# CH32F203K8T6-R0.net
KiCad netlist of a schematic drawn in Altium Designer
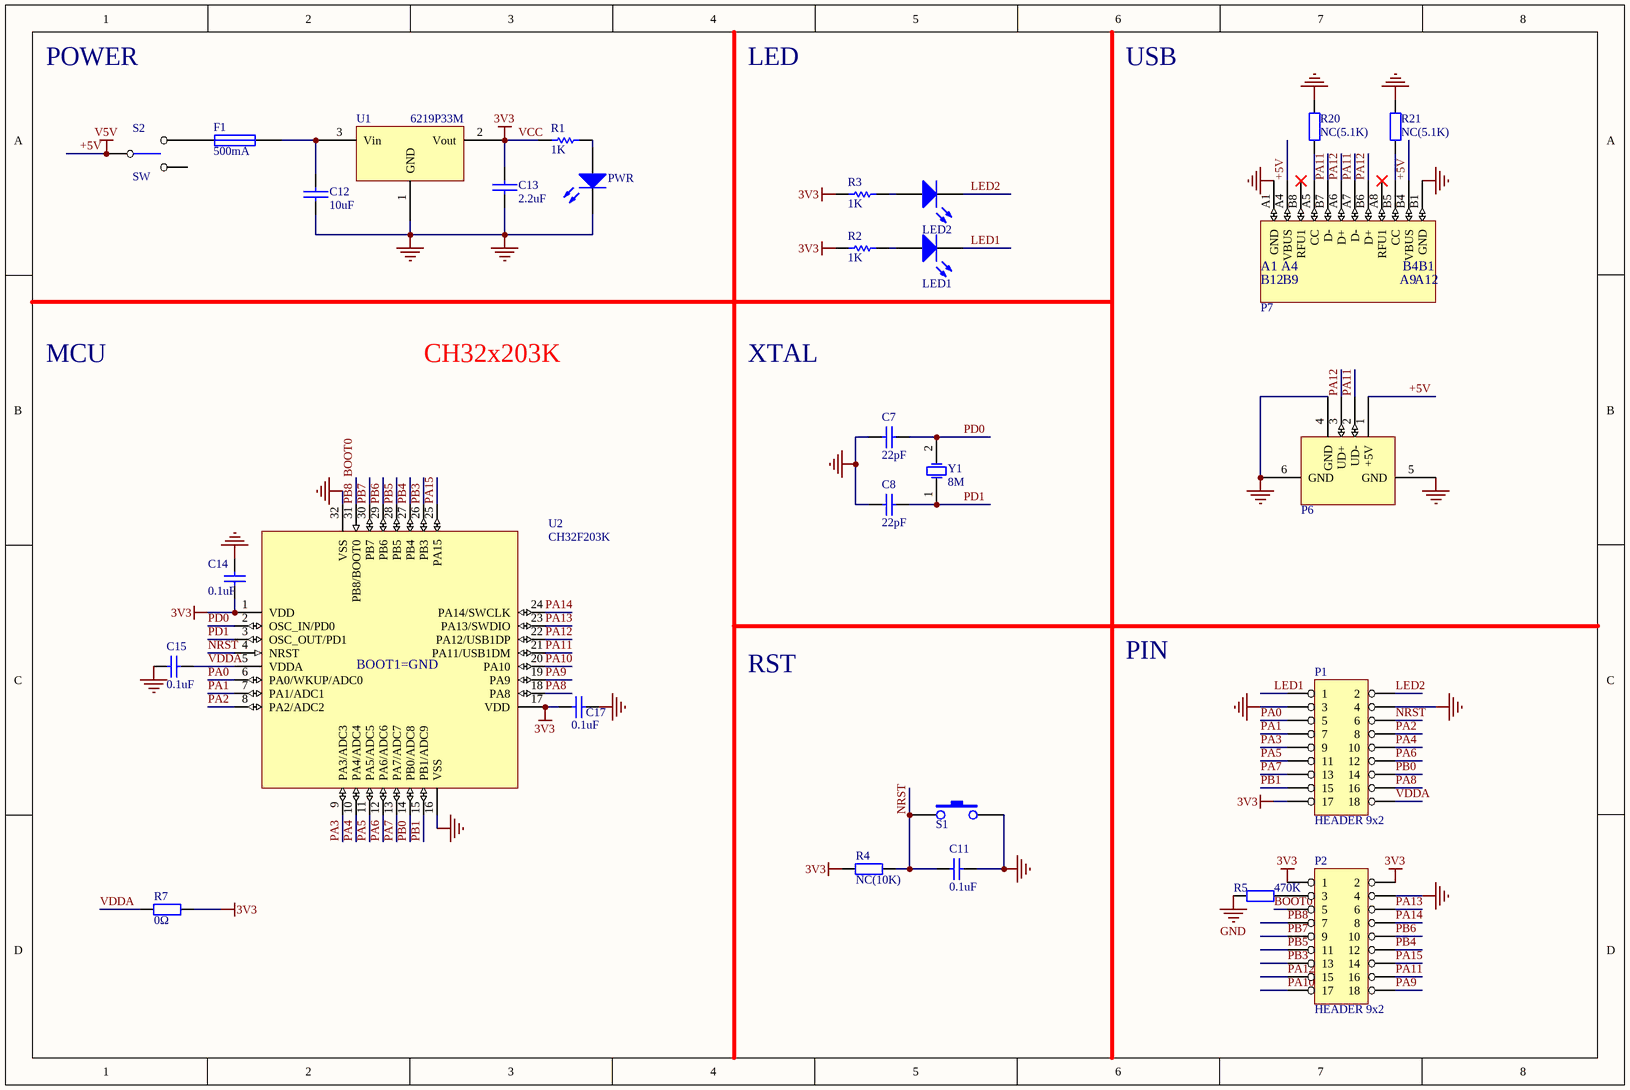
[diagram p0: CH32F203K8T6-R0.SchDoc]

(export (version "E")
  (design (tool "Eeschema 10.0.6"))
  (components
    (comp (ref "C7")
      (value "22pF")
      (footprint "0603_C")
      (description "Capacitor")
      (fields (field (name "PUBLISHER") "Altium Limited"))
      (libsource (lib "*") (part "Cap"))
    )
    (comp (ref "C8")
      (value "22pF")
      (footprint "0603_C")
      (description "Capacitor")
      (fields (field (name "PUBLISHER") "Altium Limited"))
      (libsource (lib "*") (part "Cap"))
    )
    (comp (ref "C11")
      (value "0.1uF")
      (footprint "0603_C")
      (description "Capacitor")
      (fields (field (name "PUBLISHER") "Altium Limited"))
      (libsource (lib "*") (part "Cap"))
    )
    (comp (ref "C12")
      (value "10uF")
      (footprint "3216_C")
      (description "Capacitor")
      (libsource (lib "wch_sch_others") (part "CAP"))
    )
    (comp (ref "C13")
      (value "2.2uF")
      (footprint "0603_C")
      (description "Capacitor")
      (libsource (lib "wch_sch_others") (part "CAP"))
    )
    (comp (ref "C14")
      (value "0.1uF")
      (footprint "0603_C")
      (description "Capacitor")
      (fields (field (name "PUBLISHER") "Altium Limited"))
      (libsource (lib "*") (part "Cap"))
    )
    (comp (ref "C15")
      (value "0.1uF")
      (footprint "0603_C")
      (description "Capacitor")
      (fields (field (name "PUBLISHER") "Altium Limited"))
      (libsource (lib "*") (part "Cap"))
    )
    (comp (ref "C17")
      (value "0.1uF")
      (footprint "0603_C")
      (description "Capacitor")
      (fields (field (name "PUBLISHER") "Altium Limited"))
      (libsource (lib "*") (part "Cap"))
    )
    (comp (ref "F1")
      (value "500mA")
      (footprint "0603")
      (description "Fuse")
      (libsource (lib "*") (part "FUSE1"))
    )
    (comp (ref "LED1")
      (value "LED1   blue")
      (footprint "0603+")
      (description "Typical INFRARED GaAs LED")
      (fields (field (name "PUBLISHER") "Altium Limited"))
      (libsource (lib "*") (part "LED0"))
    )
    (comp (ref "LED2")
      (value "LED2  blue")
      (footprint "0603+")
      (description "Typical INFRARED GaAs LED")
      (fields (field (name "PUBLISHER") "Altium Limited"))
      (libsource (lib "*") (part "LED0"))
    )
    (comp (ref "P1")
      (value "HEADER 9x2")
      (footprint "MYPCB:IDC18-2.54MM")
      (description "Header, 9-Pin, Dual row")
      (libsource (lib "wch_sch_others") (part "HEADER 9x2"))
    )
    (comp (ref "P2")
      (value "HEADER 9x2")
      (footprint "MYPCB:IDC18-2.54MM")
      (description "Header, 9-Pin, Dual row")
      (libsource (lib "wch_sch_others") (part "HEADER 9x2"))
    )
    (comp (ref "P6")
      (value "USB_A")
      (footprint "USBAF")
      (description "USB Port")
      (libsource (lib "*") (part "USB"))
    )
    (comp (ref "P7")
      (value "TYPE-C")
      (footprint "TYPE-C-Receptacle-2.0")
      (libsource (lib "*") (part "TYPE-C1"))
    )
    (comp (ref "PWR")
      (value "POWER  red")
      (footprint "0603+")
      (description "Typical INFRARED GaAs LED")
      (fields (field (name "PUBLISHER") "Altium Limited"))
      (libsource (lib "*") (part "LED0"))
    )
    (comp (ref "R1")
      (value "1K")
      (footprint "0603")
      (description "Semiconductor Resistor")
      (fields (field (name "PUBLISHER") "Altium Limited"))
      (libsource (lib "*") (part "Res Semi"))
    )
    (comp (ref "R2")
      (value "1K")
      (footprint "0603")
      (description "Semiconductor Resistor")
      (fields (field (name "PUBLISHER") "Altium Limited"))
      (libsource (lib "*") (part "Res Semi"))
    )
    (comp (ref "R3")
      (value "1K")
      (footprint "0603")
      (description "Semiconductor Resistor")
      (fields (field (name "PUBLISHER") "Altium Limited"))
      (libsource (lib "*") (part "Res Semi"))
    )
    (comp (ref "R4")
      (value "NC(10K)")
      (footprint "0603")
      (description "Resistor")
      (fields (field (name "PUBLISHER") "Altium Limited"))
      (libsource (lib "*") (part "Res2"))
    )
    (comp (ref "R5")
      (value "470K")
      (footprint "0603")
      (description "Resistor")
      (fields (field (name "PUBLISHER") "Altium Limited"))
      (libsource (lib "") (part "Res2_1"))
    )
    (comp (ref "R7")
      (value "0Ω")
      (footprint "0603")
      (description "Resistor")
      (fields (field (name "PUBLISHER") "Altium Limited"))
      (libsource (lib "*") (part "Res2"))
    )
    (comp (ref "R20")
      (value "NC(5.1K)")
      (footprint "0603")
      (description "Resistor")
      (libsource (lib "Miscellaneous Devices") (part "Res2"))
    )
    (comp (ref "R21")
      (value "NC(5.1K)")
      (footprint "0603")
      (description "Resistor")
      (libsource (lib "Miscellaneous Devices") (part "Res2"))
    )
    (comp (ref "S1") (value "RST") (footprint "SMD_6.1x3.65x2.5mm-KEY") (libsource (lib "*") (part "KEY")))
    (comp (ref "S2") (value "SW") (footprint "KEY2") (libsource (lib "*") (part "SW")))
    (comp (ref "U1")
      (value "6219P33M")
      (footprint "SOT-23")
      (libsource (lib "wch_sch_others") (part "6219P33M"))
    )
    (comp (ref "U2")
      (value "CH32F203K")
      (footprint "LQFP32")
      (description "ARM M3 LMD-MCU, 144MHz, USB FS, CAN")
      (libsource (lib "CHXXX") (part "CH32F203K"))
    )
    (comp (ref "Y1")
      (value "8M")
      (footprint "XT_AT49")
      (description "Crystal Oscillator")
      (fields (field (name "PUBLISHER") "Altium Limited"))
      (libsource (lib "*") (part "XTAL"))
    )
  )
  (nets
    (net (code "2") (name "/BOOT0") (class "Default")
      (node (ref "P2") (pin "5") (pinfunction "5_5") (pintype "passive"))
      (node (ref "P2") (pin "7") (pinfunction "7_7") (pintype "passive"))
      (node (ref "U2") (pin "31") (pinfunction "PB8/BOOT0_31") (pintype "input"))
    )
    (net (code "3") (name "/LED1") (class "Default")
      (node (ref "LED1") (pin "2") (pinfunction "K_2") (pintype "passive"))
      (node (ref "P1") (pin "1") (pinfunction "1_1") (pintype "passive"))
    )
    (net (code "4") (name "/LED2") (class "Default")
      (node (ref "LED2") (pin "2") (pinfunction "K_2") (pintype "passive"))
      (node (ref "P1") (pin "2") (pinfunction "2_2") (pintype "passive"))
    )
    (net (code "5") (name "/NRST") (class "Default")
      (node (ref "C11") (pin "2") (pinfunction "2_2") (pintype "passive"))
      (node (ref "P1") (pin "6") (pinfunction "6_6") (pintype "passive"))
      (node (ref "R4") (pin "1") (pinfunction "1_1") (pintype "passive"))
      (node (ref "S1") (pin "1") (pinfunction "1_1") (pintype "passive"))
      (node (ref "U2") (pin "4") (pinfunction "NRST_4") (pintype "input"))
    )
    (net (code "6") (name "/PA0") (class "Default")
      (node (ref "P1") (pin "5") (pinfunction "5_5") (pintype "passive"))
      (node (ref "U2") (pin "6") (pinfunction "PA0/WKUP/ADC0_6") (pintype "bidirectional"))
    )
    (net (code "7") (name "/PA1") (class "Default")
      (node (ref "P1") (pin "7") (pinfunction "7_7") (pintype "passive"))
      (node (ref "U2") (pin "7") (pinfunction "PA1/ADC1_7") (pintype "bidirectional"))
    )
    (net (code "8") (name "/PA2") (class "Default")
      (node (ref "P1") (pin "8") (pinfunction "8_8") (pintype "passive"))
      (node (ref "U2") (pin "8") (pinfunction "PA2/ADC2_8") (pintype "bidirectional"))
    )
    (net (code "9") (name "/PA3") (class "Default")
      (node (ref "P1") (pin "9") (pinfunction "9_9") (pintype "passive"))
      (node (ref "U2") (pin "9") (pinfunction "PA3/ADC3_9") (pintype "bidirectional"))
    )
    (net (code "10") (name "/PA4") (class "Default")
      (node (ref "P1") (pin "10") (pinfunction "10_10") (pintype "passive"))
      (node (ref "U2") (pin "10") (pinfunction "PA4/ADC4_10") (pintype "bidirectional"))
    )
    (net (code "11") (name "/PA5") (class "Default")
      (node (ref "P1") (pin "11") (pinfunction "11_11") (pintype "passive"))
      (node (ref "U2") (pin "11") (pinfunction "PA5/ADC5_11") (pintype "bidirectional"))
    )
    (net (code "12") (name "/PA6") (class "Default")
      (node (ref "P1") (pin "12") (pinfunction "12_12") (pintype "passive"))
      (node (ref "U2") (pin "12") (pinfunction "PA6/ADC6_12") (pintype "bidirectional"))
    )
    (net (code "13") (name "/PA7") (class "Default")
      (node (ref "P1") (pin "13") (pinfunction "13_13") (pintype "passive"))
      (node (ref "U2") (pin "13") (pinfunction "PA7/ADC7_13") (pintype "bidirectional"))
    )
    (net (code "14") (name "/PA8") (class "Default")
      (node (ref "P1") (pin "16") (pinfunction "16_16") (pintype "passive"))
      (node (ref "U2") (pin "18") (pinfunction "PA8_18") (pintype "bidirectional"))
    )
    (net (code "15") (name "/PA9") (class "Default")
      (node (ref "P2") (pin "18") (pinfunction "18_18") (pintype "passive"))
      (node (ref "U2") (pin "19") (pinfunction "PA9_19") (pintype "bidirectional"))
    )
    (net (code "16") (name "/PA10") (class "Default")
      (node (ref "P2") (pin "17") (pinfunction "17_17") (pintype "passive"))
      (node (ref "U2") (pin "20") (pinfunction "PA10_20") (pintype "bidirectional"))
    )
    (net (code "17") (name "/PA11") (class "Default")
      (node (ref "P2") (pin "16") (pinfunction "16_16") (pintype "passive"))
      (node (ref "P6") (pin "2") (pinfunction "UD-_2") (pintype "bidirectional"))
      (node (ref "P7") (pin "A7") (pinfunction "D-_A7") (pintype "bidirectional"))
      (node (ref "P7") (pin "B7") (pinfunction "D-_B7") (pintype "bidirectional"))
      (node (ref "U2") (pin "21") (pinfunction "PA11/USB1DM_21") (pintype "bidirectional"))
    )
    (net (code "18") (name "/PA12") (class "Default")
      (node (ref "P2") (pin "15") (pinfunction "15_15") (pintype "passive"))
      (node (ref "P6") (pin "3") (pinfunction "UD+_3") (pintype "bidirectional"))
      (node (ref "P7") (pin "A6") (pinfunction "D+_A6") (pintype "bidirectional"))
      (node (ref "P7") (pin "B6") (pinfunction "D+_B6") (pintype "bidirectional"))
      (node (ref "U2") (pin "22") (pinfunction "PA12/USB1DP_22") (pintype "bidirectional"))
    )
    (net (code "19") (name "/PA13") (class "Default")
      (node (ref "P2") (pin "6") (pinfunction "6_6") (pintype "passive"))
      (node (ref "U2") (pin "23") (pinfunction "PA13/SWDIO_23") (pintype "bidirectional"))
    )
    (net (code "20") (name "/PA14") (class "Default")
      (node (ref "P2") (pin "8") (pinfunction "8_8") (pintype "passive"))
      (node (ref "U2") (pin "24") (pinfunction "PA14/SWCLK_24") (pintype "bidirectional"))
    )
    (net (code "21") (name "/PA15") (class "Default")
      (node (ref "P2") (pin "14") (pinfunction "14_14") (pintype "passive"))
      (node (ref "U2") (pin "25") (pinfunction "PA15_25") (pintype "bidirectional"))
    )
    (net (code "22") (name "/PB0") (class "Default")
      (node (ref "P1") (pin "14") (pinfunction "14_14") (pintype "passive"))
      (node (ref "U2") (pin "14") (pinfunction "PB0/ADC8_14") (pintype "bidirectional"))
    )
    (net (code "23") (name "/PB1") (class "Default")
      (node (ref "P1") (pin "15") (pinfunction "15_15") (pintype "passive"))
      (node (ref "U2") (pin "15") (pinfunction "PB1/ADC9_15") (pintype "bidirectional"))
    )
    (net (code "24") (name "/PB3") (class "Default")
      (node (ref "P2") (pin "13") (pinfunction "13_13") (pintype "passive"))
      (node (ref "U2") (pin "26") (pinfunction "PB3_26") (pintype "bidirectional"))
    )
    (net (code "25") (name "/PB4") (class "Default")
      (node (ref "P2") (pin "12") (pinfunction "12_12") (pintype "passive"))
      (node (ref "U2") (pin "27") (pinfunction "PB4_27") (pintype "bidirectional"))
    )
    (net (code "26") (name "/PB5") (class "Default")
      (node (ref "P2") (pin "11") (pinfunction "11_11") (pintype "passive"))
      (node (ref "U2") (pin "28") (pinfunction "PB5_28") (pintype "bidirectional"))
    )
    (net (code "27") (name "/PB6") (class "Default")
      (node (ref "P2") (pin "10") (pinfunction "10_10") (pintype "passive"))
      (node (ref "U2") (pin "29") (pinfunction "PB6_29") (pintype "bidirectional"))
    )
    (net (code "28") (name "/PB7") (class "Default")
      (node (ref "P2") (pin "9") (pinfunction "9_9") (pintype "passive"))
      (node (ref "U2") (pin "30") (pinfunction "PB7_30") (pintype "bidirectional"))
    )
    (net (code "29") (name "/PD0") (class "Default")
      (node (ref "C7") (pin "2") (pinfunction "2_2") (pintype "passive"))
      (node (ref "U2") (pin "2") (pinfunction "OSC_IN/PD0_2") (pintype "bidirectional"))
      (node (ref "Y1") (pin "2") (pinfunction "OSC2_2") (pintype "passive"))
    )
    (net (code "30") (name "/PD1") (class "Default")
      (node (ref "C8") (pin "2") (pinfunction "2_2") (pintype "passive"))
      (node (ref "U2") (pin "3") (pinfunction "OSC_OUT/PD1_3") (pintype "bidirectional"))
      (node (ref "Y1") (pin "1") (pinfunction "OSC1_1") (pintype "passive"))
    )
    (net (code "31") (name "/VDDA") (class "Default")
      (node (ref "C15") (pin "1") (pinfunction "1_1") (pintype "passive"))
      (node (ref "P1") (pin "18") (pinfunction "18_18") (pintype "passive"))
      (node (ref "R7") (pin "2") (pinfunction "2_2") (pintype "passive"))
      (node (ref "U2") (pin "5") (pinfunction "VDDA_5") (pintype "power_in"))
    )
    (net (code "32") (name "3V3") (class "Default")
      (node (ref "C13") (pin "2") (pinfunction "2_2") (pintype "passive"))
      (node (ref "C14") (pin "2") (pinfunction "2_2") (pintype "passive"))
      (node (ref "C17") (pin "1") (pinfunction "1_1") (pintype "passive"))
      (node (ref "P1") (pin "17") (pinfunction "17_17") (pintype "passive"))
      (node (ref "P2") (pin "1") (pinfunction "1_1") (pintype "passive"))
      (node (ref "P2") (pin "2") (pinfunction "2_2") (pintype "passive"))
      (node (ref "R1") (pin "2") (pinfunction "2_2") (pintype "passive"))
      (node (ref "R2") (pin "1") (pinfunction "1_1") (pintype "passive"))
      (node (ref "R3") (pin "1") (pinfunction "1_1") (pintype "passive"))
      (node (ref "R4") (pin "2") (pinfunction "2_2") (pintype "passive"))
      (node (ref "R7") (pin "1") (pinfunction "1_1") (pintype "passive"))
      (node (ref "U1") (pin "2") (pinfunction "Vout_2") (pintype "passive"))
      (node (ref "U2") (pin "1") (pinfunction "VDD_1") (pintype "power_in"))
      (node (ref "U2") (pin "17") (pinfunction "VDD_17") (pintype "power_in"))
    )
    (net (code "33") (name "GND") (class "Default")
      (node (ref "C11") (pin "1") (pinfunction "1_1") (pintype "passive"))
      (node (ref "C12") (pin "2") (pinfunction "2_2") (pintype "passive"))
      (node (ref "C13") (pin "1") (pinfunction "1_1") (pintype "passive"))
      (node (ref "C14") (pin "1") (pinfunction "1_1") (pintype "passive"))
      (node (ref "C15") (pin "2") (pinfunction "2_2") (pintype "passive"))
      (node (ref "C17") (pin "2") (pinfunction "2_2") (pintype "passive"))
      (node (ref "C7") (pin "1") (pinfunction "1_1") (pintype "passive"))
      (node (ref "C8") (pin "1") (pinfunction "1_1") (pintype "passive"))
      (node (ref "P1") (pin "3") (pinfunction "3_3") (pintype "passive"))
      (node (ref "P1") (pin "4") (pinfunction "4_4") (pintype "passive"))
      (node (ref "P2") (pin "4") (pinfunction "4_4") (pintype "passive"))
      (node (ref "P6") (pin "4") (pinfunction "GND_4") (pintype "power_in"))
      (node (ref "P6") (pin "5") (pinfunction "GND_5") (pintype "power_in"))
      (node (ref "P6") (pin "6") (pinfunction "GND_6") (pintype "power_in"))
      (node (ref "P7") (pin "A1") (pinfunction "GND_A1") (pintype "bidirectional"))
      (node (ref "P7") (pin "B1") (pinfunction "GND_B1") (pintype "bidirectional"))
      (node (ref "PWR") (pin "2") (pinfunction "K_2") (pintype "passive"))
      (node (ref "R20") (pin "2") (pinfunction "2_2") (pintype "passive"))
      (node (ref "R21") (pin "2") (pinfunction "2_2") (pintype "passive"))
      (node (ref "R5") (pin "1") (pinfunction "1_1") (pintype "passive"))
      (node (ref "S1") (pin "2") (pinfunction "2_2") (pintype "passive"))
      (node (ref "U1") (pin "1") (pinfunction "GND_1") (pintype "passive"))
      (node (ref "U2") (pin "16") (pinfunction "VSS_16") (pintype "power_in"))
      (node (ref "U2") (pin "32") (pinfunction "VSS_32") (pintype "power_in"))
    )
    (net (code "34") (name "Net-(F1-Pad1)") (class "Default")
      (node (ref "F1") (pin "1") (pinfunction "1_1") (pintype "passive"))
      (node (ref "S2") (pin "3") (pinfunction "3_3") (pintype "passive"))
    )
    (net (code "35") (name "Net-(LED1-A)") (class "Default")
      (node (ref "LED1") (pin "1") (pinfunction "A_1") (pintype "passive"))
      (node (ref "R2") (pin "2") (pinfunction "2_2") (pintype "passive"))
    )
    (net (code "36") (name "Net-(LED2-A)") (class "Default")
      (node (ref "LED2") (pin "1") (pinfunction "A_1") (pintype "passive"))
      (node (ref "R3") (pin "2") (pinfunction "2_2") (pintype "passive"))
    )
    (net (code "37") (name "Net-(P2-Pad3)") (class "Default")
      (node (ref "P2") (pin "3") (pinfunction "3_3") (pintype "passive"))
      (node (ref "R5") (pin "2") (pinfunction "2_2") (pintype "passive"))
    )
    (net (code "38") (name "Net-(P7-CC-PadA5)") (class "Default")
      (node (ref "P7") (pin "A5") (pinfunction "CC_A5") (pintype "bidirectional"))
      (node (ref "R20") (pin "1") (pinfunction "1_1") (pintype "passive"))
    )
    (net (code "39") (name "Net-(P7-CC-PadB5)") (class "Default")
      (node (ref "P7") (pin "B5") (pinfunction "CC_B5") (pintype "bidirectional"))
      (node (ref "R21") (pin "1") (pinfunction "1_1") (pintype "passive"))
    )
    (net (code "40") (name "Net-(PWR-A)") (class "Default")
      (node (ref "PWR") (pin "1") (pinfunction "A_1") (pintype "passive"))
      (node (ref "R1") (pin "1") (pinfunction "1_1") (pintype "passive"))
    )
    (net (code "41") (name "Net-(U1-Vin)") (class "Default")
      (node (ref "C12") (pin "1") (pinfunction "1_1") (pintype "passive"))
      (node (ref "F1") (pin "2") (pinfunction "2_2") (pintype "passive"))
      (node (ref "U1") (pin "3") (pinfunction "Vin_3") (pintype "passive"))
    )
    (net (code "42") (name "V5V") (class "Default")
      (node (ref "P6") (pin "1") (pinfunction "+5V_1") (pintype "power_in"))
      (node (ref "P7") (pin "A4") (pinfunction "VBUS_A4") (pintype "bidirectional"))
      (node (ref "P7") (pin "B4") (pinfunction "VBUS_B4") (pintype "bidirectional"))
      (node (ref "S2") (pin "1") (pinfunction "1_1") (pintype "passive"))
    )
    (net (code "43") (name "unconnected-(P7-RFU1-PadA8)") (class "Default")
      (node (ref "P7") (pin "A8") (pinfunction "RFU1_A8") (pintype "bidirectional+no_connect"))
    )
    (net (code "44") (name "unconnected-(P7-RFU1-PadB8)") (class "Default")
      (node (ref "P7") (pin "B8") (pinfunction "RFU1_B8") (pintype "bidirectional+no_connect"))
    )
    (net (code "45") (name "unconnected-(S2-Pad2)") (class "Default")
      (node (ref "S2") (pin "2") (pinfunction "2_2") (pintype "passive"))
    )
  )
)
